# I2cLevelShifter.net
KiCad netlist of a schematic drawn in Altium Designer
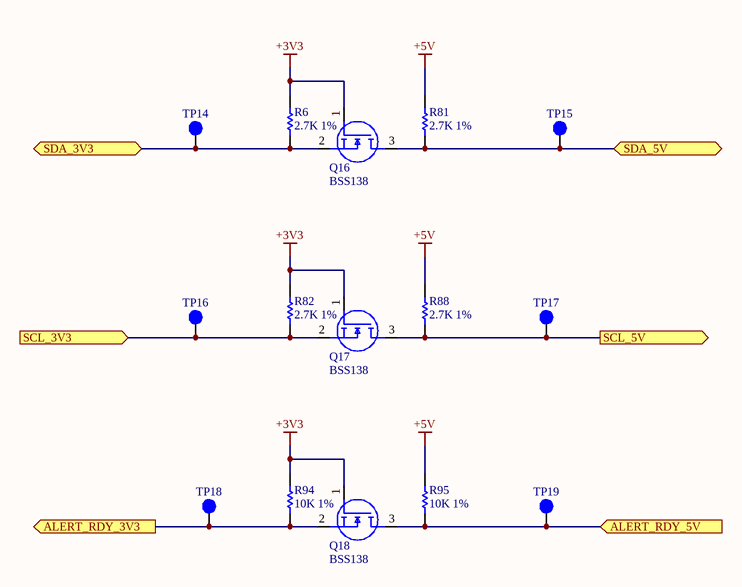
[diagram p0: I2cLevelShifter.SchDoc]

(export (version "E")
  (design (tool "Eeschema 10.0.6"))
  (components
    (comp (ref "Q16")
      (value "BSS138")
      (footprint "SOT-23-3")
      (description "MOSFET N-CH 50V 220MA SOT-23")
      (fields (field (name "MANUFACTURER") "ON Semiconductor / Fairchild"))
      (libsource (lib "RP3_V302") (part "BSS138"))
    )
    (comp (ref "Q17")
      (value "BSS138")
      (footprint "SOT-23-3")
      (description "MOSFET N-CH 50V 220MA SOT-23")
      (fields (field (name "MANUFACTURER") "ON Semiconductor / Fairchild"))
      (libsource (lib "RP3_V302") (part "BSS138"))
    )
    (comp (ref "Q18")
      (value "BSS138")
      (footprint "SOT-23-3")
      (description "MOSFET N-CH 50V 220MA SOT-23")
      (fields (field (name "MANUFACTURER") "ON Semiconductor / Fairchild"))
      (libsource (lib "RP3_V302") (part "BSS138"))
    )
    (comp (ref "R6")
      (value "2.7K 1%")
      (footprint "R0805")
      (description "RES SMD 2.7K OHM 1% 1/8W 0805")
      (fields
        (field (name "MANUFACTURER") "Yageo")
        (field (name "MANUFACTURER PART NUMBER") "AC0805FR-072K7L")
      )
      (libsource (lib "MCx") (part "AC0805FR-072K7L"))
    )
    (comp (ref "R81")
      (value "2.7K 1%")
      (footprint "R0805")
      (description "RES SMD 2.7K OHM 1% 1/8W 0805")
      (fields
        (field (name "MANUFACTURER") "Yageo")
        (field (name "MANUFACTURER PART NUMBER") "AC0805FR-072K7L")
      )
      (libsource (lib "MCx") (part "AC0805FR-072K7L"))
    )
    (comp (ref "R82")
      (value "2.7K 1%")
      (footprint "R0805")
      (description "RES SMD 2.7K OHM 1% 1/8W 0805")
      (fields
        (field (name "MANUFACTURER") "Yageo")
        (field (name "MANUFACTURER PART NUMBER") "AC0805FR-072K7L")
      )
      (libsource (lib "MCx") (part "AC0805FR-072K7L"))
    )
    (comp (ref "R88")
      (value "2.7K 1%")
      (footprint "R0805")
      (description "RES SMD 2.7K OHM 1% 1/8W 0805")
      (fields
        (field (name "MANUFACTURER") "Yageo")
        (field (name "MANUFACTURER PART NUMBER") "AC0805FR-072K7L")
      )
      (libsource (lib "MCx") (part "AC0805FR-072K7L"))
    )
    (comp (ref "R94")
      (value "10K 1%")
      (footprint "R0805")
      (fields
        (field (name "MANUFACTURER") "Vishay")
        (field (name "MANUFACTURER PART NUMBER") "CRCW080510K0FKEA")
        (field (name "TOLERANCE") "1%")
      )
      (libsource (lib "MCx") (part "CRCW080510K0FKEA"))
    )
    (comp (ref "R95")
      (value "10K 1%")
      (footprint "R0805")
      (fields
        (field (name "MANUFACTURER") "Vishay")
        (field (name "MANUFACTURER PART NUMBER") "CRCW080510K0FKEA")
        (field (name "TOLERANCE") "1%")
      )
      (libsource (lib "MCx") (part "CRCW080510K0FKEA"))
    )
    (comp (ref "TP14")
      (value "T")
      (footprint "MC1:TESTPOINTSMD_1x1MM")
      (description "SMD Test Point")
      (libsource (lib "MC1") (part "TestPoint_SMD_1x1"))
    )
    (comp (ref "TP15")
      (value "T")
      (footprint "MC1:TESTPOINTSMD_1x1MM")
      (description "SMD Test Point")
      (libsource (lib "MC1") (part "TestPoint_SMD_1x1"))
    )
    (comp (ref "TP16")
      (value "T")
      (footprint "MC1:TESTPOINTSMD_1x1MM")
      (description "SMD Test Point")
      (libsource (lib "MC1") (part "TestPoint_SMD_1x1"))
    )
    (comp (ref "TP17")
      (value "T")
      (footprint "MC1:TESTPOINTSMD_1x1MM")
      (description "SMD Test Point")
      (libsource (lib "MC1") (part "TestPoint_SMD_1x1"))
    )
    (comp (ref "TP18")
      (value "T")
      (footprint "MC1:TESTPOINTSMD_1x1MM")
      (description "SMD Test Point")
      (libsource (lib "MC1") (part "TestPoint_SMD_1x1"))
    )
    (comp (ref "TP19")
      (value "T")
      (footprint "MC1:TESTPOINTSMD_1x1MM")
      (description "SMD Test Point")
      (libsource (lib "MC1") (part "TestPoint_SMD_1x1"))
    )
  )
  (nets
    (net (code "1") (name "+3V3") (class "Default")
      (node (ref "Q16") (pin "1") (pinfunction "G_1") (pintype "passive"))
      (node (ref "Q17") (pin "1") (pinfunction "G_1") (pintype "passive"))
      (node (ref "Q18") (pin "1") (pinfunction "G_1") (pintype "passive"))
      (node (ref "R6") (pin "2") (pinfunction "2_2") (pintype "passive"))
      (node (ref "R82") (pin "2") (pinfunction "2_2") (pintype "passive"))
      (node (ref "R94") (pin "2") (pinfunction "2_2") (pintype "passive"))
    )
    (net (code "2") (name "+5V") (class "Default")
      (node (ref "R81") (pin "2") (pinfunction "2_2") (pintype "passive"))
      (node (ref "R88") (pin "2") (pinfunction "2_2") (pintype "passive"))
      (node (ref "R95") (pin "2") (pinfunction "2_2") (pintype "passive"))
    )
    (net (code "3") (name "/ALERT_RDY_3V3") (class "Default")
      (node (ref "Q18") (pin "2") (pinfunction "S_2") (pintype "passive"))
      (node (ref "R94") (pin "1") (pinfunction "1_1") (pintype "passive"))
      (node (ref "TP18") (pin "1") (pinfunction "1_1") (pintype "passive"))
    )
    (net (code "4") (name "/ALERT_RDY_5V") (class "Default")
      (node (ref "Q18") (pin "3") (pinfunction "D_3") (pintype "passive"))
      (node (ref "R95") (pin "1") (pinfunction "1_1") (pintype "passive"))
      (node (ref "TP19") (pin "1") (pinfunction "1_1") (pintype "passive"))
    )
    (net (code "5") (name "/SCL_3V3") (class "Default")
      (node (ref "Q17") (pin "2") (pinfunction "S_2") (pintype "passive"))
      (node (ref "R82") (pin "1") (pinfunction "1_1") (pintype "passive"))
      (node (ref "TP16") (pin "1") (pinfunction "1_1") (pintype "passive"))
    )
    (net (code "6") (name "/SCL_5V") (class "Default")
      (node (ref "Q17") (pin "3") (pinfunction "D_3") (pintype "passive"))
      (node (ref "R88") (pin "1") (pinfunction "1_1") (pintype "passive"))
      (node (ref "TP17") (pin "1") (pinfunction "1_1") (pintype "passive"))
    )
    (net (code "7") (name "/SDA_3V3") (class "Default")
      (node (ref "Q16") (pin "2") (pinfunction "S_2") (pintype "passive"))
      (node (ref "R6") (pin "1") (pinfunction "1_1") (pintype "passive"))
      (node (ref "TP14") (pin "1") (pinfunction "1_1") (pintype "passive"))
    )
    (net (code "8") (name "/SDA_5V") (class "Default")
      (node (ref "Q16") (pin "3") (pinfunction "D_3") (pintype "passive"))
      (node (ref "R81") (pin "1") (pinfunction "1_1") (pintype "passive"))
      (node (ref "TP15") (pin "1") (pinfunction "1_1") (pintype "passive"))
    )
  )
)
